# ch32v307_feather_v6.net
KiCad netlist of a schematic drawn in EAGLE
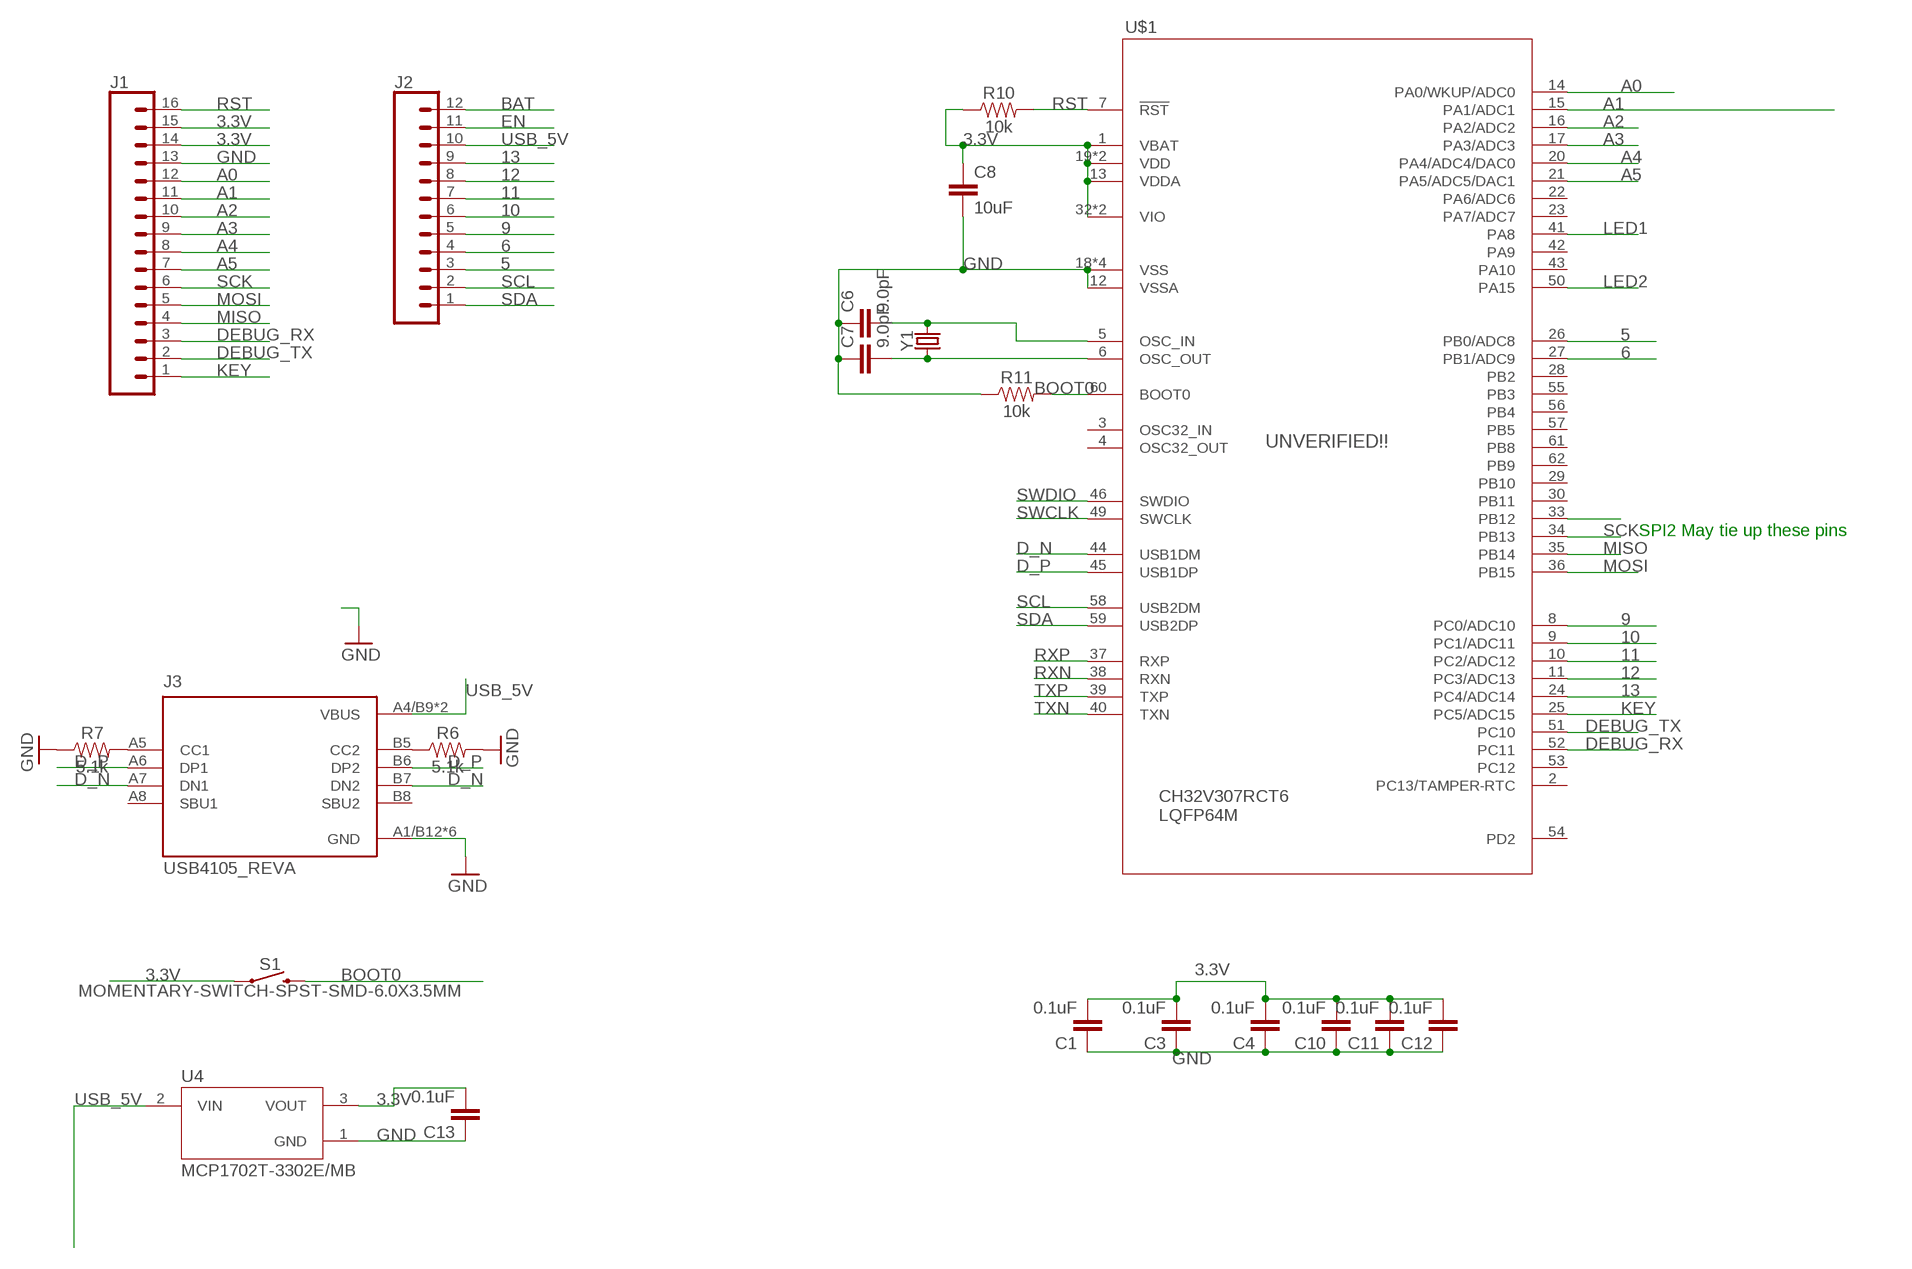
[diagram p0: schematic, sheet 1]

(export (version "E")
  (design (tool "Eeschema 10.0.6"))
  (components
    (comp (ref "C1")
      (value "0.1uF")
      (footprint "eagle-import:0603-CAP")
      (libsource (lib "eagle-import") (part "CAP0603-CAP"))
    )
    (comp (ref "C3")
      (value "0.1uF")
      (footprint "eagle-import:0603-CAP")
      (libsource (lib "eagle-import") (part "CAP0603-CAP"))
    )
    (comp (ref "C4")
      (value "0.1uF")
      (footprint "eagle-import:0603-CAP")
      (libsource (lib "eagle-import") (part "CAP0603-CAP"))
    )
    (comp (ref "C6")
      (value "9.0pF")
      (footprint "eagle-import:0603")
      (libsource (lib "eagle-import") (part "9.0PF-0603-50V-10%"))
    )
    (comp (ref "C7")
      (value "9.0pF")
      (footprint "eagle-import:0603")
      (libsource (lib "eagle-import") (part "9.0PF-0603-50V-10%"))
    )
    (comp (ref "C8")
      (value "10uF")
      (footprint "eagle-import:1210")
      (libsource (lib "eagle-import") (part "10UF-1210-50V-20%"))
    )
    (comp (ref "C10")
      (value "0.1uF")
      (footprint "eagle-import:0603-CAP")
      (libsource (lib "eagle-import") (part "CAP0603-CAP"))
    )
    (comp (ref "C11")
      (value "0.1uF")
      (footprint "eagle-import:0603-CAP")
      (libsource (lib "eagle-import") (part "CAP0603-CAP"))
    )
    (comp (ref "C12")
      (value "0.1uF")
      (footprint "eagle-import:0603-CAP")
      (libsource (lib "eagle-import") (part "CAP0603-CAP"))
    )
    (comp (ref "C13")
      (value "0.1uF")
      (footprint "eagle-import:0603-CAP")
      (libsource (lib "eagle-import") (part "CAP0603-CAP"))
    )
    (comp (ref "J1")
      (value "CONN_16")
      (footprint "eagle-import:1X16")
      (libsource (lib "eagle-import") (part "CONN_16"))
    )
    (comp (ref "J2")
      (value "CONN_12")
      (footprint "eagle-import:1X12")
      (libsource (lib "eagle-import") (part "CONN_12"))
    )
    (comp (ref "J3")
      (value "USB4105_REVA")
      (footprint "eagle-import:GCT_USB4105_REVA")
      (fields (field (name "MANUFACTURER") "GCT"))
      (libsource (lib "eagle-import") (part "USB4105_REVA"))
    )
    (comp (ref "R6")
      (value "5.1k")
      (footprint "eagle-import:0603")
      (libsource (lib "eagle-import") (part "RESISTOR0603"))
    )
    (comp (ref "R7")
      (value "5.1k")
      (footprint "eagle-import:0603")
      (libsource (lib "eagle-import") (part "RESISTOR0603"))
    )
    (comp (ref "R10")
      (value "10k")
      (footprint "eagle-import:0603")
      (libsource (lib "eagle-import") (part "10KOHM-0603-1/10W-1%"))
    )
    (comp (ref "R11")
      (value "10k")
      (footprint "eagle-import:0603")
      (libsource (lib "eagle-import") (part "10KOHM-0603-1/10W-1%"))
    )
    (comp (ref "S1")
      (value "MOMENTARY-SWITCH-SPST-SMD-6.0X3.5MM")
      (footprint "eagle-import:TACTILE_SWITCH_SMD_6.0X3.5MM")
      (libsource (lib "eagle-import") (part "MOMENTARY-SWITCH-SPST-SMD-6.0X3.5MM"))
    )
    (comp (ref "U$1")
      (value "CH32V307RCT6")
      (footprint "eagle-import:LQFP64M")
      (libsource (lib "eagle-import") (part "CH32V307RCT6"))
    )
    (comp (ref "U4")
      (value "MCP1702T-3302E/MB")
      (footprint "eagle-import:REG_MCP1702T-3302E_MB")
      (fields (field (name "MANUFACTURER") "Microchip"))
      (libsource (lib "eagle-import") (part "MCP1702T-3302E/MB"))
    )
    (comp (ref "Y1")
      (value "CRYSTALSMD-3.2X2.5")
      (footprint "eagle-import:CRYSTAL-SMD-3.2X2.5MM")
      (libsource (lib "eagle-import") (part "CRYSTALSMD-3.2X2.5"))
    )
  )
  (nets
    (net (code "1") (name "/3.3V") (class "Default")
      (node (ref "C1") (pin "2") (pinfunction "2_2") (pintype "passive"))
      (node (ref "C10") (pin "2") (pinfunction "2_2") (pintype "passive"))
      (node (ref "C11") (pin "2") (pinfunction "2_2") (pintype "passive"))
      (node (ref "C12") (pin "2") (pinfunction "2_2") (pintype "passive"))
      (node (ref "C13") (pin "2") (pinfunction "2_2") (pintype "passive"))
      (node (ref "C3") (pin "2") (pinfunction "2_2") (pintype "passive"))
      (node (ref "C4") (pin "2") (pinfunction "2_2") (pintype "passive"))
      (node (ref "C8") (pin "1") (pinfunction "1_1") (pintype "passive"))
      (node (ref "J1") (pin "14") (pinfunction "14_14") (pintype "passive"))
      (node (ref "J1") (pin "15") (pinfunction "15_15") (pintype "passive"))
      (node (ref "R10") (pin "1") (pinfunction "1_1") (pintype "passive"))
      (node (ref "S1") (pin "1") (pinfunction "1_1") (pintype "passive"))
      (node (ref "U$1") (pin "1") (pinfunction "VBAT_1") (pintype "bidirectional"))
      (node (ref "U$1") (pin "13") (pinfunction "VDDA_13") (pintype "bidirectional"))
      (node (ref "U$1") (pin "19") (pinfunction "VDD_19") (pintype "bidirectional"))
      (node (ref "U$1") (pin "32") (pinfunction "VIO_32") (pintype "bidirectional"))
      (node (ref "U$1") (pin "48") (pinfunction "VDD_48") (pintype "bidirectional"))
      (node (ref "U$1") (pin "64") (pinfunction "VIO_64") (pintype "bidirectional"))
      (node (ref "U4") (pin "3") (pinfunction "VOUT_3") (pintype "output"))
    )
    (net (code "2") (name "/5") (class "Default")
      (node (ref "J2") (pin "3") (pinfunction "3_3") (pintype "passive"))
      (node (ref "U$1") (pin "26") (pinfunction "PB0/ADC8_26") (pintype "bidirectional"))
    )
    (net (code "3") (name "/6") (class "Default")
      (node (ref "J2") (pin "4") (pinfunction "4_4") (pintype "passive"))
      (node (ref "U$1") (pin "27") (pinfunction "PB1/ADC9_27") (pintype "bidirectional"))
    )
    (net (code "4") (name "/9") (class "Default")
      (node (ref "J2") (pin "5") (pinfunction "5_5") (pintype "passive"))
      (node (ref "U$1") (pin "8") (pinfunction "PC0/ADC10_8") (pintype "bidirectional"))
    )
    (net (code "5") (name "/10") (class "Default")
      (node (ref "J2") (pin "6") (pinfunction "6_6") (pintype "passive"))
      (node (ref "U$1") (pin "9") (pinfunction "PC1/ADC11_9") (pintype "bidirectional"))
    )
    (net (code "6") (name "/11") (class "Default")
      (node (ref "J2") (pin "7") (pinfunction "7_7") (pintype "passive"))
      (node (ref "U$1") (pin "10") (pinfunction "PC2/ADC12_10") (pintype "bidirectional"))
    )
    (net (code "7") (name "/12") (class "Default")
      (node (ref "J2") (pin "8") (pinfunction "8_8") (pintype "passive"))
      (node (ref "U$1") (pin "11") (pinfunction "PC3/ADC13_11") (pintype "bidirectional"))
    )
    (net (code "8") (name "/13") (class "Default")
      (node (ref "J2") (pin "9") (pinfunction "9_9") (pintype "passive"))
      (node (ref "U$1") (pin "24") (pinfunction "PC4/ADC14_24") (pintype "bidirectional"))
    )
    (net (code "9") (name "/A0") (class "Default")
      (node (ref "J1") (pin "12") (pinfunction "12_12") (pintype "passive"))
      (node (ref "U$1") (pin "14") (pinfunction "PA0/WKUP/ADC0_14") (pintype "bidirectional"))
    )
    (net (code "10") (name "/A1") (class "Default")
      (node (ref "J1") (pin "11") (pinfunction "11_11") (pintype "passive"))
      (node (ref "U$1") (pin "15") (pinfunction "PA1/ADC1_15") (pintype "bidirectional"))
    )
    (net (code "11") (name "/A2") (class "Default")
      (node (ref "J1") (pin "10") (pinfunction "10_10") (pintype "passive"))
      (node (ref "U$1") (pin "16") (pinfunction "PA2/ADC2_16") (pintype "bidirectional"))
    )
    (net (code "12") (name "/A3") (class "Default")
      (node (ref "J1") (pin "9") (pinfunction "9_9") (pintype "passive"))
      (node (ref "U$1") (pin "17") (pinfunction "PA3/ADC3_17") (pintype "bidirectional"))
    )
    (net (code "13") (name "/A4") (class "Default")
      (node (ref "J1") (pin "8") (pinfunction "8_8") (pintype "passive"))
      (node (ref "U$1") (pin "20") (pinfunction "PA4/ADC4/DAC0_20") (pintype "bidirectional"))
    )
    (net (code "14") (name "/A5") (class "Default")
      (node (ref "J1") (pin "7") (pinfunction "7_7") (pintype "passive"))
      (node (ref "U$1") (pin "21") (pinfunction "PA5/ADC5/DAC1_21") (pintype "bidirectional"))
    )
    (net (code "15") (name "/BAT") (class "Default")
      (node (ref "J2") (pin "12") (pinfunction "12_12") (pintype "passive"))
    )
    (net (code "16") (name "/BOOT0") (class "Default")
      (node (ref "R11") (pin "2") (pinfunction "2_2") (pintype "passive"))
      (node (ref "S1") (pin "2") (pinfunction "2_2") (pintype "passive"))
      (node (ref "U$1") (pin "60") (pinfunction "BOOT0_60") (pintype "bidirectional"))
    )
    (net (code "17") (name "/DEBUG_RX") (class "Default")
      (node (ref "J1") (pin "3") (pinfunction "3_3") (pintype "passive"))
      (node (ref "U$1") (pin "52") (pinfunction "PC11_52") (pintype "bidirectional"))
    )
    (net (code "18") (name "/DEBUG_TX") (class "Default")
      (node (ref "J1") (pin "2") (pinfunction "2_2") (pintype "passive"))
      (node (ref "U$1") (pin "51") (pinfunction "PC10_51") (pintype "bidirectional"))
    )
    (net (code "19") (name "/D_N") (class "Default")
      (node (ref "J3") (pin "A7") (pinfunction "DN1_A7") (pintype "bidirectional"))
      (node (ref "J3") (pin "B7") (pinfunction "DN2_B7") (pintype "bidirectional"))
      (node (ref "U$1") (pin "44") (pinfunction "USB1DM_44") (pintype "bidirectional"))
    )
    (net (code "20") (name "/D_P") (class "Default")
      (node (ref "J3") (pin "A6") (pinfunction "DP1_A6") (pintype "bidirectional"))
      (node (ref "J3") (pin "B6") (pinfunction "DP2_B6") (pintype "bidirectional"))
      (node (ref "U$1") (pin "45") (pinfunction "USB1DP_45") (pintype "bidirectional"))
    )
    (net (code "21") (name "/EN") (class "Default")
      (node (ref "J2") (pin "11") (pinfunction "11_11") (pintype "passive"))
    )
    (net (code "22") (name "/KEY") (class "Default")
      (node (ref "J1") (pin "1") (pinfunction "1_1") (pintype "passive"))
      (node (ref "U$1") (pin "25") (pinfunction "PC5/ADC15_25") (pintype "bidirectional"))
    )
    (net (code "23") (name "/LED1") (class "Default")
      (node (ref "U$1") (pin "41") (pinfunction "PA8_41") (pintype "bidirectional"))
    )
    (net (code "24") (name "/LED2") (class "Default")
      (node (ref "U$1") (pin "50") (pinfunction "PA15_50") (pintype "bidirectional"))
    )
    (net (code "25") (name "/MISO") (class "Default")
      (node (ref "J1") (pin "4") (pinfunction "4_4") (pintype "passive"))
      (node (ref "U$1") (pin "35") (pinfunction "PB14_35") (pintype "bidirectional"))
    )
    (net (code "26") (name "/MOSI") (class "Default")
      (node (ref "J1") (pin "5") (pinfunction "5_5") (pintype "passive"))
      (node (ref "U$1") (pin "36") (pinfunction "PB15_36") (pintype "bidirectional"))
    )
    (net (code "27") (name "/RST") (class "Default")
      (node (ref "J1") (pin "16") (pinfunction "16_16") (pintype "passive"))
      (node (ref "R10") (pin "2") (pinfunction "2_2") (pintype "passive"))
      (node (ref "U$1") (pin "7") (pinfunction "~{RST}_7") (pintype "bidirectional"))
    )
    (net (code "28") (name "/RXN") (class "Default")
      (node (ref "U$1") (pin "38") (pinfunction "RXN_38") (pintype "bidirectional"))
    )
    (net (code "29") (name "/RXP") (class "Default")
      (node (ref "U$1") (pin "37") (pinfunction "RXP_37") (pintype "bidirectional"))
    )
    (net (code "30") (name "/SCK") (class "Default")
      (node (ref "J1") (pin "6") (pinfunction "6_6") (pintype "passive"))
      (node (ref "U$1") (pin "34") (pinfunction "PB13_34") (pintype "bidirectional"))
    )
    (net (code "31") (name "/SCL") (class "Default")
      (node (ref "J2") (pin "2") (pinfunction "2_2") (pintype "passive"))
      (node (ref "U$1") (pin "58") (pinfunction "USB2DM_58") (pintype "bidirectional"))
    )
    (net (code "32") (name "/SDA") (class "Default")
      (node (ref "J2") (pin "1") (pinfunction "1_1") (pintype "passive"))
      (node (ref "U$1") (pin "59") (pinfunction "USB2DP_59") (pintype "bidirectional"))
    )
    (net (code "33") (name "/SWCLK") (class "Default")
      (node (ref "U$1") (pin "49") (pinfunction "SWCLK_49") (pintype "bidirectional"))
    )
    (net (code "34") (name "/SWDIO") (class "Default")
      (node (ref "U$1") (pin "46") (pinfunction "SWDIO_46") (pintype "bidirectional"))
    )
    (net (code "35") (name "/TXN") (class "Default")
      (node (ref "U$1") (pin "40") (pinfunction "TXN_40") (pintype "bidirectional"))
    )
    (net (code "36") (name "/TXP") (class "Default")
      (node (ref "U$1") (pin "39") (pinfunction "TXP_39") (pintype "bidirectional"))
    )
    (net (code "37") (name "/USB_5V") (class "Default")
      (node (ref "J2") (pin "10") (pinfunction "10_10") (pintype "passive"))
      (node (ref "J3") (pin "A4/B9") (pinfunction "VBUS_A4/B9") (pintype "power_in"))
      (node (ref "J3") (pin "B4/A9") (pinfunction "VBUS_B4/A9") (pintype "power_in"))
      (node (ref "U4") (pin "2") (pinfunction "VIN_2") (pintype "input"))
    )
    (net (code "38") (name "GND") (class "Default")
      (node (ref "C1") (pin "1") (pinfunction "1_1") (pintype "passive"))
      (node (ref "C10") (pin "1") (pinfunction "1_1") (pintype "passive"))
      (node (ref "C11") (pin "1") (pinfunction "1_1") (pintype "passive"))
      (node (ref "C12") (pin "1") (pinfunction "1_1") (pintype "passive"))
      (node (ref "C13") (pin "1") (pinfunction "1_1") (pintype "passive"))
      (node (ref "C3") (pin "1") (pinfunction "1_1") (pintype "passive"))
      (node (ref "C4") (pin "1") (pinfunction "1_1") (pintype "passive"))
      (node (ref "C6") (pin "1") (pinfunction "1_1") (pintype "passive"))
      (node (ref "C7") (pin "1") (pinfunction "1_1") (pintype "passive"))
      (node (ref "C8") (pin "2") (pinfunction "2_2") (pintype "passive"))
      (node (ref "J1") (pin "13") (pinfunction "13_13") (pintype "passive"))
      (node (ref "J3") (pin "A1/B12") (pinfunction "GND_A1/B12") (pintype "power_in"))
      (node (ref "J3") (pin "B1/A12") (pinfunction "GND_B1/A12") (pintype "power_in"))
      (node (ref "J3") (pin "G1") (pinfunction "GND_G1") (pintype "power_in"))
      (node (ref "J3") (pin "G2") (pinfunction "GND_G2") (pintype "power_in"))
      (node (ref "J3") (pin "G3") (pinfunction "GND_G3") (pintype "power_in"))
      (node (ref "J3") (pin "G4") (pinfunction "GND_G4") (pintype "power_in"))
      (node (ref "R11") (pin "1") (pinfunction "1_1") (pintype "passive"))
      (node (ref "R6") (pin "2") (pinfunction "2_2") (pintype "passive"))
      (node (ref "R7") (pin "1") (pinfunction "1_1") (pintype "passive"))
      (node (ref "U$1") (pin "12") (pinfunction "VSSA_12") (pintype "bidirectional"))
      (node (ref "U$1") (pin "18") (pinfunction "VSS_18") (pintype "bidirectional"))
      (node (ref "U$1") (pin "31") (pinfunction "VSS_31") (pintype "bidirectional"))
      (node (ref "U$1") (pin "47") (pinfunction "VSS_47") (pintype "bidirectional"))
      (node (ref "U$1") (pin "63") (pinfunction "VSS_63") (pintype "bidirectional"))
      (node (ref "U4") (pin "1") (pinfunction "GND_1") (pintype "power_in"))
    )
    (net (code "39") (name "Net-(J3-CC1)") (class "Default")
      (node (ref "J3") (pin "A5") (pinfunction "CC1_A5") (pintype "bidirectional"))
      (node (ref "R7") (pin "2") (pinfunction "2_2") (pintype "passive"))
    )
    (net (code "40") (name "Net-(J3-CC2)") (class "Default")
      (node (ref "J3") (pin "B5") (pinfunction "CC2_B5") (pintype "bidirectional"))
      (node (ref "R6") (pin "1") (pinfunction "1_1") (pintype "passive"))
    )
    (net (code "41") (name "Net-(U$1-OSC_IN)") (class "Default")
      (node (ref "C6") (pin "2") (pinfunction "2_2") (pintype "passive"))
      (node (ref "U$1") (pin "5") (pinfunction "OSC_IN_5") (pintype "bidirectional"))
      (node (ref "Y1") (pin "3") (pinfunction "2_3") (pintype "passive"))
    )
    (net (code "42") (name "Net-(U$1-OSC_OUT)") (class "Default")
      (node (ref "C7") (pin "2") (pinfunction "2_2") (pintype "passive"))
      (node (ref "U$1") (pin "6") (pinfunction "OSC_OUT_6") (pintype "bidirectional"))
      (node (ref "Y1") (pin "1") (pinfunction "1_1") (pintype "passive"))
    )
    (net (code "43") (name "unconnected-(J3-SBU1-PadA8)") (class "Default")
      (node (ref "J3") (pin "A8") (pinfunction "SBU1_A8") (pintype "bidirectional"))
    )
    (net (code "44") (name "unconnected-(J3-SBU2-PadB8)") (class "Default")
      (node (ref "J3") (pin "B8") (pinfunction "SBU2_B8") (pintype "bidirectional"))
    )
    (net (code "45") (name "unconnected-(U$1-OSC32_IN-Pad3)") (class "Default")
      (node (ref "U$1") (pin "3") (pinfunction "OSC32_IN_3") (pintype "bidirectional"))
    )
    (net (code "46") (name "unconnected-(U$1-OSC32_OUT-Pad4)") (class "Default")
      (node (ref "U$1") (pin "4") (pinfunction "OSC32_OUT_4") (pintype "bidirectional"))
    )
    (net (code "47") (name "unconnected-(U$1-PA6{slash}ADC6-Pad22)") (class "Default")
      (node (ref "U$1") (pin "22") (pinfunction "PA6/ADC6_22") (pintype "bidirectional"))
    )
    (net (code "48") (name "unconnected-(U$1-PA7{slash}ADC7-Pad23)") (class "Default")
      (node (ref "U$1") (pin "23") (pinfunction "PA7/ADC7_23") (pintype "bidirectional"))
    )
    (net (code "49") (name "unconnected-(U$1-PA9-Pad42)") (class "Default")
      (node (ref "U$1") (pin "42") (pinfunction "PA9_42") (pintype "bidirectional"))
    )
    (net (code "50") (name "unconnected-(U$1-PA10-Pad43)") (class "Default")
      (node (ref "U$1") (pin "43") (pinfunction "PA10_43") (pintype "bidirectional"))
    )
    (net (code "51") (name "unconnected-(U$1-PB2-Pad28)") (class "Default")
      (node (ref "U$1") (pin "28") (pinfunction "PB2_28") (pintype "bidirectional"))
    )
    (net (code "52") (name "unconnected-(U$1-PB3-Pad55)") (class "Default")
      (node (ref "U$1") (pin "55") (pinfunction "PB3_55") (pintype "bidirectional"))
    )
    (net (code "53") (name "unconnected-(U$1-PB4-Pad56)") (class "Default")
      (node (ref "U$1") (pin "56") (pinfunction "PB4_56") (pintype "bidirectional"))
    )
    (net (code "54") (name "unconnected-(U$1-PB5-Pad57)") (class "Default")
      (node (ref "U$1") (pin "57") (pinfunction "PB5_57") (pintype "bidirectional"))
    )
    (net (code "55") (name "unconnected-(U$1-PB8-Pad61)") (class "Default")
      (node (ref "U$1") (pin "61") (pinfunction "PB8_61") (pintype "bidirectional"))
    )
    (net (code "56") (name "unconnected-(U$1-PB9-Pad62)") (class "Default")
      (node (ref "U$1") (pin "62") (pinfunction "PB9_62") (pintype "bidirectional"))
    )
    (net (code "57") (name "unconnected-(U$1-PB10-Pad29)") (class "Default")
      (node (ref "U$1") (pin "29") (pinfunction "PB10_29") (pintype "bidirectional"))
    )
    (net (code "58") (name "unconnected-(U$1-PB11-Pad30)") (class "Default")
      (node (ref "U$1") (pin "30") (pinfunction "PB11_30") (pintype "bidirectional"))
    )
    (net (code "59") (name "unconnected-(U$1-PB12-Pad33)") (class "Default")
      (node (ref "U$1") (pin "33") (pinfunction "PB12_33") (pintype "bidirectional"))
    )
    (net (code "60") (name "unconnected-(U$1-PC12-Pad53)") (class "Default")
      (node (ref "U$1") (pin "53") (pinfunction "PC12_53") (pintype "bidirectional"))
    )
    (net (code "61") (name "unconnected-(U$1-PC13{slash}TAMPER-RTC-Pad2)") (class "Default")
      (node (ref "U$1") (pin "2") (pinfunction "PC13/TAMPER-RTC_2") (pintype "bidirectional"))
    )
    (net (code "62") (name "unconnected-(U$1-PD2-Pad54)") (class "Default")
      (node (ref "U$1") (pin "54") (pinfunction "PD2_54") (pintype "bidirectional"))
    )
  )
)
